# HumidTempSleep_Feather_001.net
KiCad netlist of a schematic drawn in EAGLE
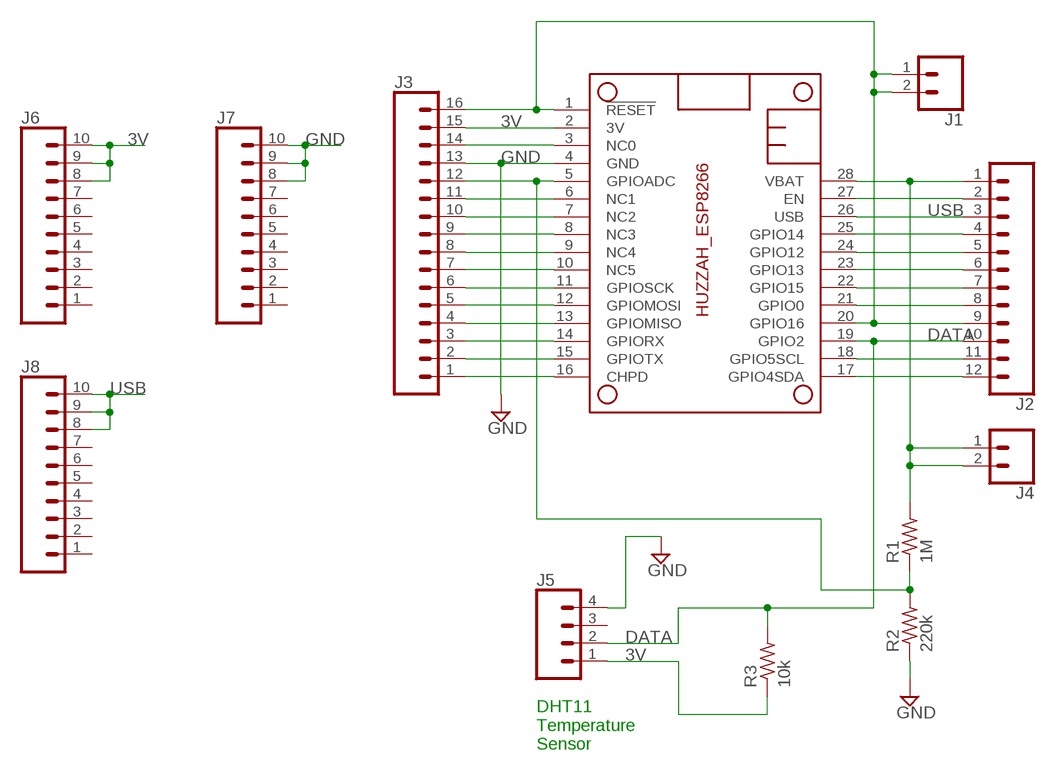
[diagram p0: schematic, sheet 1]

(export (version "E")
  (design (tool "Eeschema 10.0.6"))
  (components
    (comp (ref "J1")
      (value "CONN_02")
      (footprint "eagle-import:1X02")
      (libsource (lib "eagle-import") (part "CONN_02"))
    )
    (comp (ref "J2")
      (value "CONN_12")
      (footprint "eagle-import:1X12")
      (libsource (lib "eagle-import") (part "CONN_12"))
    )
    (comp (ref "J3")
      (value "CONN_16")
      (footprint "eagle-import:1X16")
      (libsource (lib "eagle-import") (part "CONN_16"))
    )
    (comp (ref "J4")
      (value "CONN_02")
      (footprint "eagle-import:1X02")
      (libsource (lib "eagle-import") (part "CONN_02"))
    )
    (comp (ref "J5")
      (value "CONN_04PTH")
      (footprint "eagle-import:1X04")
      (libsource (lib "eagle-import") (part "CONN_04PTH"))
    )
    (comp (ref "J6")
      (value "CONN_10\"")
      (footprint "eagle-import:1X10")
      (libsource (lib "eagle-import") (part "CONN_10{dblquote}"))
    )
    (comp (ref "J7")
      (value "CONN_10\"")
      (footprint "eagle-import:1X10")
      (libsource (lib "eagle-import") (part "CONN_10{dblquote}"))
    )
    (comp (ref "J8")
      (value "CONN_10\"")
      (footprint "eagle-import:1X10")
      (libsource (lib "eagle-import") (part "CONN_10{dblquote}"))
    )
    (comp (ref "MS2")
      (value "FEATHERWING")
      (footprint "eagle-import:FEATHERWING")
      (libsource (lib "eagle-import") (part "FEATHERWING"))
    )
    (comp (ref "R1")
      (value "1M")
      (footprint "eagle-import:R0805")
      (libsource (lib "eagle-import") (part "R-US_R0805"))
    )
    (comp (ref "R2")
      (value "220k")
      (footprint "eagle-import:R0805")
      (libsource (lib "eagle-import") (part "R-US_R0805"))
    )
    (comp (ref "R3")
      (value "10k")
      (footprint "eagle-import:R0805")
      (libsource (lib "eagle-import") (part "R-US_R0805"))
    )
  )
  (nets
    (net (code "1") (name "/3V") (class "Default")
      (node (ref "J3") (pin "15") (pinfunction "15_15") (pintype "passive"))
      (node (ref "J5") (pin "1") (pinfunction "1_1") (pintype "passive"))
      (node (ref "J6") (pin "10") (pinfunction "10_10") (pintype "passive"))
      (node (ref "J6") (pin "8") (pinfunction "8_8") (pintype "passive"))
      (node (ref "J6") (pin "9") (pinfunction "9_9") (pintype "passive"))
      (node (ref "MS2") (pin "2") (pinfunction "3V_2") (pintype "power_in"))
      (node (ref "R3") (pin "1") (pinfunction "1_1") (pintype "passive"))
    )
    (net (code "2") (name "/DATA") (class "Default")
      (node (ref "J2") (pin "10") (pinfunction "10_10") (pintype "passive"))
      (node (ref "J5") (pin "2") (pinfunction "2_2") (pintype "passive"))
      (node (ref "MS2") (pin "19") (pinfunction "GPIO2_19") (pintype "bidirectional"))
      (node (ref "R3") (pin "2") (pinfunction "2_2") (pintype "passive"))
    )
    (net (code "3") (name "/USB") (class "Default")
      (node (ref "J2") (pin "3") (pinfunction "3_3") (pintype "passive"))
      (node (ref "J8") (pin "10") (pinfunction "10_10") (pintype "passive"))
      (node (ref "J8") (pin "8") (pinfunction "8_8") (pintype "passive"))
      (node (ref "J8") (pin "9") (pinfunction "9_9") (pintype "passive"))
      (node (ref "MS2") (pin "26") (pinfunction "USB_26") (pintype "power_in"))
    )
    (net (code "4") (name "GND") (class "Default")
      (node (ref "J3") (pin "13") (pinfunction "13_13") (pintype "passive"))
      (node (ref "J5") (pin "4") (pinfunction "4_4") (pintype "passive"))
      (node (ref "J7") (pin "10") (pinfunction "10_10") (pintype "passive"))
      (node (ref "J7") (pin "8") (pinfunction "8_8") (pintype "passive"))
      (node (ref "J7") (pin "9") (pinfunction "9_9") (pintype "passive"))
      (node (ref "MS2") (pin "4") (pinfunction "GND_4") (pintype "power_in"))
      (node (ref "R2") (pin "1") (pinfunction "1_1") (pintype "passive"))
    )
    (net (code "5") (name "Net-(MS2-CHPD)") (class "Default")
      (node (ref "J3") (pin "1") (pinfunction "1_1") (pintype "passive"))
      (node (ref "MS2") (pin "16") (pinfunction "CHPD_16") (pintype "passive"))
    )
    (net (code "6") (name "Net-(MS2-EN)") (class "Default")
      (node (ref "J2") (pin "2") (pinfunction "2_2") (pintype "passive"))
      (node (ref "MS2") (pin "27") (pinfunction "EN_27") (pintype "passive"))
    )
    (net (code "7") (name "Net-(MS2-GPIO0)") (class "Default")
      (node (ref "J2") (pin "8") (pinfunction "8_8") (pintype "passive"))
      (node (ref "MS2") (pin "21") (pinfunction "GPIO0_21") (pintype "bidirectional"))
    )
    (net (code "8") (name "Net-(MS2-GPIO4SDA)") (class "Default")
      (node (ref "J2") (pin "12") (pinfunction "12_12") (pintype "passive"))
      (node (ref "MS2") (pin "17") (pinfunction "GPIO4SDA_17") (pintype "bidirectional"))
    )
    (net (code "9") (name "Net-(MS2-GPIO5SCL)") (class "Default")
      (node (ref "J2") (pin "11") (pinfunction "11_11") (pintype "passive"))
      (node (ref "MS2") (pin "18") (pinfunction "GPIO5SCL_18") (pintype "bidirectional"))
    )
    (net (code "10") (name "Net-(MS2-GPIO12)") (class "Default")
      (node (ref "J2") (pin "5") (pinfunction "5_5") (pintype "passive"))
      (node (ref "MS2") (pin "24") (pinfunction "GPIO12_24") (pintype "bidirectional"))
    )
    (net (code "11") (name "Net-(MS2-GPIO13)") (class "Default")
      (node (ref "J2") (pin "6") (pinfunction "6_6") (pintype "passive"))
      (node (ref "MS2") (pin "23") (pinfunction "GPIO13_23") (pintype "bidirectional"))
    )
    (net (code "12") (name "Net-(MS2-GPIO14)") (class "Default")
      (node (ref "J2") (pin "4") (pinfunction "4_4") (pintype "passive"))
      (node (ref "MS2") (pin "25") (pinfunction "GPIO14_25") (pintype "bidirectional"))
    )
    (net (code "13") (name "Net-(MS2-GPIO15)") (class "Default")
      (node (ref "J2") (pin "7") (pinfunction "7_7") (pintype "passive"))
      (node (ref "MS2") (pin "22") (pinfunction "GPIO15_22") (pintype "bidirectional"))
    )
    (net (code "14") (name "Net-(MS2-GPIO16)") (class "Default")
      (node (ref "J1") (pin "1") (pinfunction "1_1") (pintype "passive"))
      (node (ref "J1") (pin "2") (pinfunction "2_2") (pintype "passive"))
      (node (ref "J2") (pin "9") (pinfunction "9_9") (pintype "passive"))
      (node (ref "J3") (pin "16") (pinfunction "16_16") (pintype "passive"))
      (node (ref "MS2") (pin "1") (pinfunction "~{RESET}_1") (pintype "input"))
      (node (ref "MS2") (pin "20") (pinfunction "GPIO16_20") (pintype "bidirectional"))
    )
    (net (code "15") (name "Net-(MS2-GPIOADC)") (class "Default")
      (node (ref "J3") (pin "12") (pinfunction "12_12") (pintype "passive"))
      (node (ref "MS2") (pin "5") (pinfunction "GPIOADC_5") (pintype "bidirectional"))
      (node (ref "R1") (pin "1") (pinfunction "1_1") (pintype "passive"))
      (node (ref "R2") (pin "2") (pinfunction "2_2") (pintype "passive"))
    )
    (net (code "16") (name "Net-(MS2-GPIOMISO)") (class "Default")
      (node (ref "J3") (pin "4") (pinfunction "4_4") (pintype "passive"))
      (node (ref "MS2") (pin "13") (pinfunction "GPIOMISO_13") (pintype "bidirectional"))
    )
    (net (code "17") (name "Net-(MS2-GPIOMOSI)") (class "Default")
      (node (ref "J3") (pin "5") (pinfunction "5_5") (pintype "passive"))
      (node (ref "MS2") (pin "12") (pinfunction "GPIOMOSI_12") (pintype "bidirectional"))
    )
    (net (code "18") (name "Net-(MS2-GPIORX)") (class "Default")
      (node (ref "J3") (pin "3") (pinfunction "3_3") (pintype "passive"))
      (node (ref "MS2") (pin "14") (pinfunction "GPIORX_14") (pintype "bidirectional"))
    )
    (net (code "19") (name "Net-(MS2-GPIOSCK)") (class "Default")
      (node (ref "J3") (pin "6") (pinfunction "6_6") (pintype "passive"))
      (node (ref "MS2") (pin "11") (pinfunction "GPIOSCK_11") (pintype "bidirectional"))
    )
    (net (code "20") (name "Net-(MS2-GPIOTX)") (class "Default")
      (node (ref "J3") (pin "2") (pinfunction "2_2") (pintype "passive"))
      (node (ref "MS2") (pin "15") (pinfunction "GPIOTX_15") (pintype "bidirectional"))
    )
    (net (code "21") (name "Net-(MS2-NC0)") (class "Default")
      (node (ref "J3") (pin "14") (pinfunction "14_14") (pintype "passive"))
      (node (ref "MS2") (pin "3") (pinfunction "NC0_3") (pintype "passive"))
    )
    (net (code "22") (name "Net-(MS2-NC1)") (class "Default")
      (node (ref "J3") (pin "11") (pinfunction "11_11") (pintype "passive"))
      (node (ref "MS2") (pin "6") (pinfunction "NC1_6") (pintype "bidirectional"))
    )
    (net (code "23") (name "Net-(MS2-NC2)") (class "Default")
      (node (ref "J3") (pin "10") (pinfunction "10_10") (pintype "passive"))
      (node (ref "MS2") (pin "7") (pinfunction "NC2_7") (pintype "bidirectional"))
    )
    (net (code "24") (name "Net-(MS2-NC3)") (class "Default")
      (node (ref "J3") (pin "9") (pinfunction "9_9") (pintype "passive"))
      (node (ref "MS2") (pin "8") (pinfunction "NC3_8") (pintype "bidirectional"))
    )
    (net (code "25") (name "Net-(MS2-NC4)") (class "Default")
      (node (ref "J3") (pin "8") (pinfunction "8_8") (pintype "passive"))
      (node (ref "MS2") (pin "9") (pinfunction "NC4_9") (pintype "bidirectional"))
    )
    (net (code "26") (name "Net-(MS2-NC5)") (class "Default")
      (node (ref "J3") (pin "7") (pinfunction "7_7") (pintype "passive"))
      (node (ref "MS2") (pin "10") (pinfunction "NC5_10") (pintype "bidirectional"))
    )
    (net (code "27") (name "Net-(MS2-VBAT)") (class "Default")
      (node (ref "J2") (pin "1") (pinfunction "1_1") (pintype "passive"))
      (node (ref "J4") (pin "1") (pinfunction "1_1") (pintype "passive"))
      (node (ref "J4") (pin "2") (pinfunction "2_2") (pintype "passive"))
      (node (ref "MS2") (pin "28") (pinfunction "VBAT_28") (pintype "power_in"))
      (node (ref "R1") (pin "2") (pinfunction "2_2") (pintype "passive"))
    )
    (net (code "28") (name "unconnected-(J5-Pad3)") (class "Default")
      (node (ref "J5") (pin "3") (pinfunction "3_3") (pintype "passive"))
    )
    (net (code "29") (name "unconnected-(J6-Pad1)") (class "Default")
      (node (ref "J6") (pin "1") (pinfunction "1_1") (pintype "passive"))
    )
    (net (code "30") (name "unconnected-(J6-Pad2)") (class "Default")
      (node (ref "J6") (pin "2") (pinfunction "2_2") (pintype "passive"))
    )
    (net (code "31") (name "unconnected-(J6-Pad3)") (class "Default")
      (node (ref "J6") (pin "3") (pinfunction "3_3") (pintype "passive"))
    )
    (net (code "32") (name "unconnected-(J6-Pad4)") (class "Default")
      (node (ref "J6") (pin "4") (pinfunction "4_4") (pintype "passive"))
    )
    (net (code "33") (name "unconnected-(J6-Pad5)") (class "Default")
      (node (ref "J6") (pin "5") (pinfunction "5_5") (pintype "passive"))
    )
    (net (code "34") (name "unconnected-(J6-Pad6)") (class "Default")
      (node (ref "J6") (pin "6") (pinfunction "6_6") (pintype "passive"))
    )
    (net (code "35") (name "unconnected-(J6-Pad7)") (class "Default")
      (node (ref "J6") (pin "7") (pinfunction "7_7") (pintype "passive"))
    )
    (net (code "36") (name "unconnected-(J7-Pad1)") (class "Default")
      (node (ref "J7") (pin "1") (pinfunction "1_1") (pintype "passive"))
    )
    (net (code "37") (name "unconnected-(J7-Pad2)") (class "Default")
      (node (ref "J7") (pin "2") (pinfunction "2_2") (pintype "passive"))
    )
    (net (code "38") (name "unconnected-(J7-Pad3)") (class "Default")
      (node (ref "J7") (pin "3") (pinfunction "3_3") (pintype "passive"))
    )
    (net (code "39") (name "unconnected-(J7-Pad4)") (class "Default")
      (node (ref "J7") (pin "4") (pinfunction "4_4") (pintype "passive"))
    )
    (net (code "40") (name "unconnected-(J7-Pad5)") (class "Default")
      (node (ref "J7") (pin "5") (pinfunction "5_5") (pintype "passive"))
    )
    (net (code "41") (name "unconnected-(J7-Pad6)") (class "Default")
      (node (ref "J7") (pin "6") (pinfunction "6_6") (pintype "passive"))
    )
    (net (code "42") (name "unconnected-(J7-Pad7)") (class "Default")
      (node (ref "J7") (pin "7") (pinfunction "7_7") (pintype "passive"))
    )
    (net (code "43") (name "unconnected-(J8-Pad1)") (class "Default")
      (node (ref "J8") (pin "1") (pinfunction "1_1") (pintype "passive"))
    )
    (net (code "44") (name "unconnected-(J8-Pad2)") (class "Default")
      (node (ref "J8") (pin "2") (pinfunction "2_2") (pintype "passive"))
    )
    (net (code "45") (name "unconnected-(J8-Pad3)") (class "Default")
      (node (ref "J8") (pin "3") (pinfunction "3_3") (pintype "passive"))
    )
    (net (code "46") (name "unconnected-(J8-Pad4)") (class "Default")
      (node (ref "J8") (pin "4") (pinfunction "4_4") (pintype "passive"))
    )
    (net (code "47") (name "unconnected-(J8-Pad5)") (class "Default")
      (node (ref "J8") (pin "5") (pinfunction "5_5") (pintype "passive"))
    )
    (net (code "48") (name "unconnected-(J8-Pad6)") (class "Default")
      (node (ref "J8") (pin "6") (pinfunction "6_6") (pintype "passive"))
    )
    (net (code "49") (name "unconnected-(J8-Pad7)") (class "Default")
      (node (ref "J8") (pin "7") (pinfunction "7_7") (pintype "passive"))
    )
  )
)
